# synth-zodiac-pisces-vco-mod.net
KiCad netlist of a schematic drawn in EAGLE
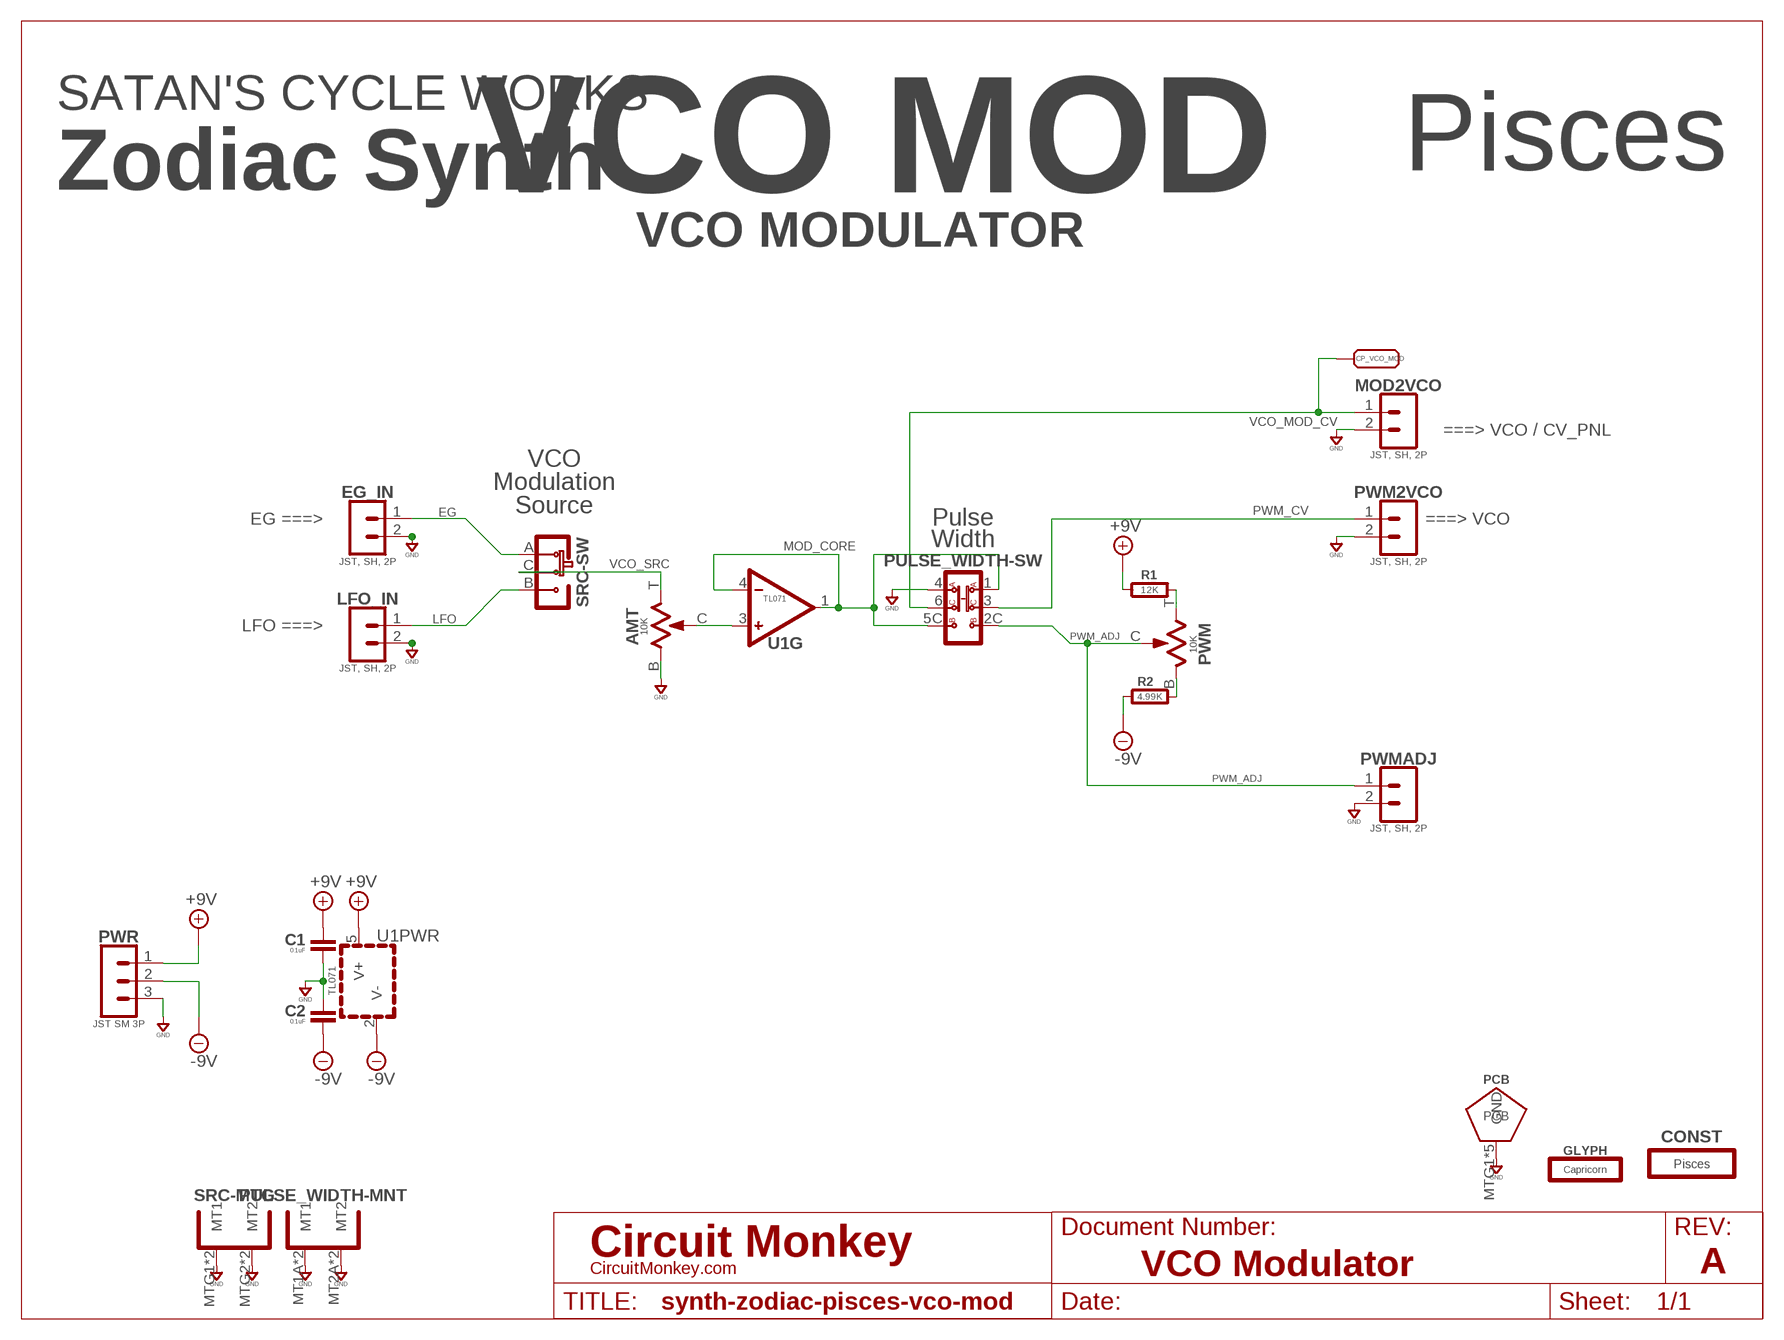
[diagram p0: schematic, sheet 1]

(export (version "E")
  (design (tool "Eeschema 10.0.6"))
  (components
    (comp (ref "AMT")
      (value "10K")
      (footprint "eagle-import:POT-RV9110")
      (fields (field (name "MFR") "Tayda") (field (name "MPN") "RV9110NO-OS15A00"))
      (libsource (lib "eagle-import") (part "TRIMPOT9MM_PCB_SHAFT"))
    )
    (comp (ref "C1")
      (value "0.1uF")
      (footprint "eagle-import:0603-CAP")
      (libsource (lib "eagle-import") (part "CAPACITOR0603"))
    )
    (comp (ref "C2")
      (value "0.1uF")
      (footprint "eagle-import:0603-CAP")
      (libsource (lib "eagle-import") (part "CAPACITOR0603"))
    )
    (comp (ref "CONST")
      (value "Pisces")
      (footprint "eagle-import:PISCES-CONST")
      (libsource (lib "eagle-import") (part "CONSTELLATION-PISCES"))
    )
    (comp (ref "CP_VCO_MOD")
      (value "PADSMD-070X070")
      (footprint "eagle-import:SMD-070MIL")
      (libsource (lib "eagle-import") (part "PADSMD-070X070"))
    )
    (comp (ref "EG_IN")
      (value "JST, SH, 2P")
      (footprint "eagle-import:BM02B-SRSS-TB")
      (fields (field (name "MFR") "JST") (field (name "MPN") "BMB02B-SRSS-TB"))
      (libsource (lib "eagle-import") (part "02P-SM-VT-SMT"))
    )
    (comp (ref "GLYPH")
      (value "Capricorn")
      (footprint "eagle-import:CAPRICORN-GLYPH")
      (libsource (lib "eagle-import") (part "GLYPH-CAPRICORN"))
    )
    (comp (ref "LFO_IN")
      (value "JST, SH, 2P")
      (footprint "eagle-import:BM02B-SRSS-TB")
      (fields (field (name "MFR") "JST") (field (name "MPN") "BMB02B-SRSS-TB"))
      (libsource (lib "eagle-import") (part "02P-SM-VT-SMT"))
    )
    (comp (ref "MOD2VCO")
      (value "JST, SH, 2P")
      (footprint "eagle-import:BM02B-SRSS-TB")
      (fields (field (name "MFR") "JST") (field (name "MPN") "BMB02B-SRSS-TB"))
      (libsource (lib "eagle-import") (part "02P-SM-VT-SMT"))
    )
    (comp (ref "PCB")
      (value "PCB FAB")
      (footprint "eagle-import:PENTAGON-40MM-RAD")
      (libsource (lib "eagle-import") (part "PENTAGON-40R"))
    )
    (comp (ref "PULSE_WIDTH")
      (value "Switch, DPDT")
      (footprint "eagle-import:CK_OS202013MT5-PNL-SMT-2")
      (fields (field (name "MFR") "CK") (field (name "MPN") "OS202013MT5QN1"))
      (libsource (lib "eagle-import") (part "SLIDE-DPDT-MNTPNL-SMD-TOGGLE-ONLY"))
    )
    (comp (ref "PWM")
      (value "10K")
      (footprint "eagle-import:POT-RV9110")
      (fields (field (name "MFR") "Tayda") (field (name "MPN") "RV9110NO-OS15A00"))
      (libsource (lib "eagle-import") (part "TRIMPOT9MM_PCB_SHAFT"))
    )
    (comp (ref "PWM2VCO")
      (value "JST, SH, 2P")
      (footprint "eagle-import:BM02B-SRSS-TB")
      (fields (field (name "MFR") "JST") (field (name "MPN") "BMB02B-SRSS-TB"))
      (libsource (lib "eagle-import") (part "02P-SM-VT-SMT"))
    )
    (comp (ref "PWMADJ")
      (value "JST, SH, 2P")
      (footprint "eagle-import:BM02B-SRSS-TB")
      (fields (field (name "MFR") "JST") (field (name "MPN") "BMB02B-SRSS-TB"))
      (libsource (lib "eagle-import") (part "02P-SM-VT-SMT"))
    )
    (comp (ref "PWR")
      (value "JST SM 3P")
      (footprint "eagle-import:BM03B-SRSS-TB")
      (fields (field (name "MFR") "JST") (field (name "MPN") "BM03B-SRSS-TB"))
      (libsource (lib "eagle-import") (part "03P-SM-VT-SMT"))
    )
    (comp (ref "R1")
      (value "12K")
      (footprint "eagle-import:0603-RES")
      (libsource (lib "eagle-import") (part "RESISTOR0603"))
    )
    (comp (ref "R2")
      (value "4.99K")
      (footprint "eagle-import:0603-RES")
      (libsource (lib "eagle-import") (part "RESISTOR0603"))
    )
    (comp (ref "SRC")
      (value "SLIDE-SPDT-MNTSS-12-F45-TH-PCB-2")
      (footprint "eagle-import:SS-12-F45-PNL-SMT-2")
      (fields (field (name "MFR") "Tayda") (field (name "MPN") "A-659/A-5111/A-5104"))
      (libsource (lib "eagle-import") (part "SLIDE-SPDT-MNTSS-12-F45-TH-PCB-2"))
    )
    (comp (ref "U1")
      (value "TL071")
      (footprint "eagle-import:SOT-23-5")
      (fields (field (name "MFR") "TI") (field (name "MPN") "TL071HIDBV"))
      (libsource (lib "eagle-import") (part "SINGLE-TL071"))
    )
  )
  (nets
    (net (code "1") (name "+9V") (class "Default")
      (node (ref "C1") (pin "1") (pinfunction "1_1") (pintype "passive"))
      (node (ref "PWR") (pin "1") (pinfunction "1_1") (pintype "passive"))
      (node (ref "R1") (pin "1") (pinfunction "1_1") (pintype "passive"))
      (node (ref "U1") (pin "5") (pinfunction "V+_5") (pintype "power_in"))
    )
    (net (code "2") (name "-9V") (class "Default")
      (node (ref "C2") (pin "2") (pinfunction "2_2") (pintype "passive"))
      (node (ref "PWR") (pin "2") (pinfunction "2_2") (pintype "passive"))
      (node (ref "R2") (pin "2") (pinfunction "2_2") (pintype "passive"))
      (node (ref "U1") (pin "2") (pinfunction "V-_2") (pintype "power_in"))
    )
    (net (code "3") (name "/EG") (class "Default")
      (node (ref "EG_IN") (pin "1") (pinfunction "1_1") (pintype "passive"))
      (node (ref "SRC") (pin "A") (pinfunction "A_A") (pintype "bidirectional"))
    )
    (net (code "4") (name "/LFO") (class "Default")
      (node (ref "LFO_IN") (pin "1") (pinfunction "1_1") (pintype "passive"))
      (node (ref "SRC") (pin "B") (pinfunction "B_B") (pintype "bidirectional"))
    )
    (net (code "5") (name "/MOD_CORE") (class "Default")
      (node (ref "PULSE_WIDTH") (pin "1") (pinfunction "1A_1") (pintype "bidirectional"))
      (node (ref "PULSE_WIDTH") (pin "5C") (pinfunction "2B_5C") (pintype "bidirectional"))
      (node (ref "U1") (pin "1") (pinfunction "OUT_1") (pintype "output"))
      (node (ref "U1") (pin "4") (pinfunction "-_4") (pintype "input"))
    )
    (net (code "6") (name "/PWM_ADJ") (class "Default")
      (node (ref "PULSE_WIDTH") (pin "2C") (pinfunction "1B_2C") (pintype "bidirectional"))
      (node (ref "PWM") (pin "C") (pinfunction "2_C") (pintype "passive"))
      (node (ref "PWMADJ") (pin "1") (pinfunction "1_1") (pintype "passive"))
    )
    (net (code "7") (name "/PWM_CV") (class "Default")
      (node (ref "PULSE_WIDTH") (pin "3") (pinfunction "1C_3") (pintype "bidirectional"))
      (node (ref "PWM2VCO") (pin "1") (pinfunction "1_1") (pintype "passive"))
    )
    (net (code "8") (name "/VCO_MOD_CV") (class "Default")
      (node (ref "CP_VCO_MOD") (pin "1") (pinfunction "PAD_1") (pintype "bidirectional"))
      (node (ref "MOD2VCO") (pin "1") (pinfunction "1_1") (pintype "passive"))
      (node (ref "PULSE_WIDTH") (pin "6") (pinfunction "2C_6") (pintype "bidirectional"))
    )
    (net (code "9") (name "/VCO_SRC") (class "Default")
      (node (ref "AMT") (pin "T") (pinfunction "3_T") (pintype "passive"))
      (node (ref "SRC") (pin "C") (pinfunction "C_C") (pintype "bidirectional"))
    )
    (net (code "10") (name "GND") (class "Default")
      (node (ref "AMT") (pin "B") (pinfunction "1_B") (pintype "passive"))
      (node (ref "C1") (pin "2") (pinfunction "2_2") (pintype "passive"))
      (node (ref "C2") (pin "1") (pinfunction "1_1") (pintype "passive"))
      (node (ref "EG_IN") (pin "2") (pinfunction "2_2") (pintype "passive"))
      (node (ref "LFO_IN") (pin "2") (pinfunction "2_2") (pintype "passive"))
      (node (ref "MOD2VCO") (pin "2") (pinfunction "2_2") (pintype "passive"))
      (node (ref "PCB") (pin "MTG1") (pinfunction "GND_MTG1") (pintype "bidirectional"))
      (node (ref "PCB") (pin "MTG2") (pinfunction "GND_MTG2") (pintype "bidirectional"))
      (node (ref "PCB") (pin "MTG3") (pinfunction "GND_MTG3") (pintype "bidirectional"))
      (node (ref "PCB") (pin "MTG4") (pinfunction "GND_MTG4") (pintype "bidirectional"))
      (node (ref "PCB") (pin "MTG5") (pinfunction "GND_MTG5") (pintype "bidirectional"))
      (node (ref "PULSE_WIDTH") (pin "4") (pinfunction "2A_4") (pintype "bidirectional"))
      (node (ref "PULSE_WIDTH") (pin "MT1A") (pinfunction "MT1_MT1A") (pintype "bidirectional"))
      (node (ref "PULSE_WIDTH") (pin "MT2A") (pinfunction "MT2_MT2A") (pintype "bidirectional"))
      (node (ref "PULSE_WIDTH") (pin "MT3A") (pinfunction "MT1_MT3A") (pintype "bidirectional"))
      (node (ref "PULSE_WIDTH") (pin "MT4A") (pinfunction "MT2_MT4A") (pintype "bidirectional"))
      (node (ref "PWM2VCO") (pin "2") (pinfunction "2_2") (pintype "passive"))
      (node (ref "PWMADJ") (pin "2") (pinfunction "2_2") (pintype "passive"))
      (node (ref "PWR") (pin "3") (pinfunction "3_3") (pintype "passive"))
      (node (ref "SRC") (pin "MTG1") (pinfunction "MT1_MTG1") (pintype "bidirectional"))
      (node (ref "SRC") (pin "MTG2") (pinfunction "MT2_MTG2") (pintype "bidirectional"))
      (node (ref "SRC") (pin "MTG3") (pinfunction "MT1_MTG3") (pintype "bidirectional"))
      (node (ref "SRC") (pin "MTG4") (pinfunction "MT2_MTG4") (pintype "bidirectional"))
    )
    (net (code "11") (name "Net-(AMT-2)") (class "Default")
      (node (ref "AMT") (pin "C") (pinfunction "2_C") (pintype "passive"))
      (node (ref "U1") (pin "3") (pinfunction "+_3") (pintype "input"))
    )
    (net (code "12") (name "Net-(PWM-1)") (class "Default")
      (node (ref "PWM") (pin "B") (pinfunction "1_B") (pintype "passive"))
      (node (ref "R2") (pin "1") (pinfunction "1_1") (pintype "passive"))
    )
    (net (code "13") (name "Net-(PWM-3)") (class "Default")
      (node (ref "PWM") (pin "T") (pinfunction "3_T") (pintype "passive"))
      (node (ref "R1") (pin "2") (pinfunction "2_2") (pintype "passive"))
    )
  )
)
